# RS232_v10.net
KiCad netlist of a schematic drawn in EAGLE
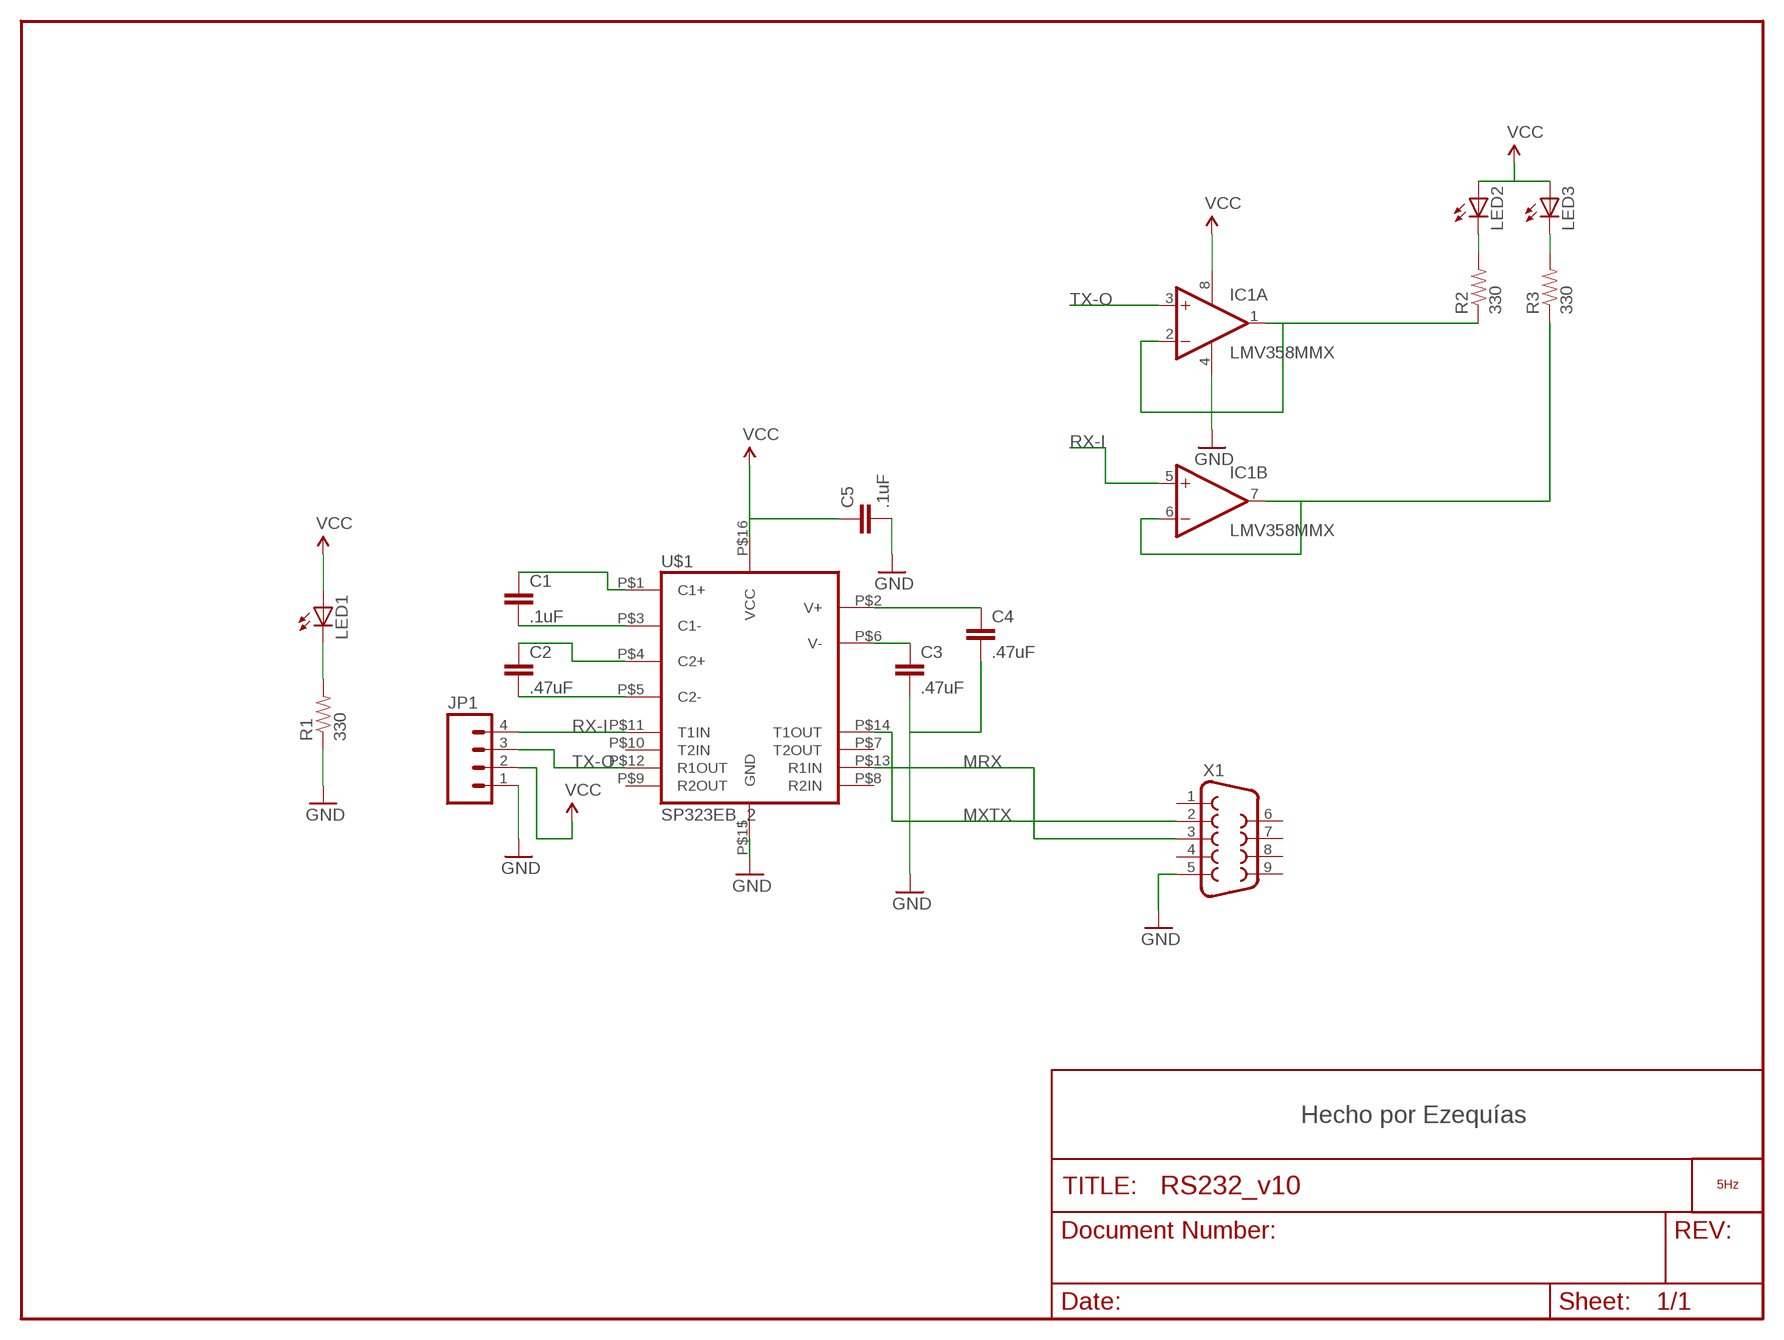
[diagram p0: schematic, sheet 1]

(export (version "E")
  (design (tool "Eeschema 10.0.6"))
  (components
    (comp (ref "C1")
      (value ".1uF")
      (footprint "eagle-import:0603-CAP")
      (libsource (lib "eagle-import") (part "CAP0603-CAP"))
    )
    (comp (ref "C2")
      (value ".47uF")
      (footprint "eagle-import:0603-CAP")
      (libsource (lib "eagle-import") (part "CAP0603-CAP"))
    )
    (comp (ref "C3")
      (value ".47uF")
      (footprint "eagle-import:0603-CAP")
      (libsource (lib "eagle-import") (part "CAP0603-CAP"))
    )
    (comp (ref "C4")
      (value ".47uF")
      (footprint "eagle-import:0603-CAP")
      (libsource (lib "eagle-import") (part "CAP0603-CAP"))
    )
    (comp (ref "C5")
      (value ".1uF")
      (footprint "eagle-import:0603-CAP")
      (libsource (lib "eagle-import") (part "CAP0603-CAP"))
    )
    (comp (ref "IC1")
      (value "LMV358MMX")
      (footprint "eagle-import:MSOP08")
      (libsource (lib "eagle-import") (part "LMV358?MMX"))
    )
    (comp (ref "JP1")
      (value "M04PTH")
      (footprint "eagle-import:1X04")
      (libsource (lib "eagle-import") (part "M04PTH"))
    )
    (comp (ref "LED1")
      (value "LED0603")
      (footprint "eagle-import:LED-0603")
      (libsource (lib "eagle-import") (part "LED0603"))
    )
    (comp (ref "LED2")
      (value "LED0603")
      (footprint "eagle-import:LED-0603")
      (libsource (lib "eagle-import") (part "LED0603"))
    )
    (comp (ref "LED3")
      (value "LED0603")
      (footprint "eagle-import:LED-0603")
      (libsource (lib "eagle-import") (part "LED0603"))
    )
    (comp (ref "LOGO1")
      (value "LOGO_5HZ_MAIN_15MM")
      (footprint "eagle-import:5HZ_LOGO_MAIN_15MM")
      (libsource (lib "eagle-import") (part "LOGO_5HZ_MAIN_15MM"))
    )
    (comp (ref "R1")
      (value "330")
      (footprint "eagle-import:0603-RES")
      (libsource (lib "eagle-import") (part "RESISTOR0603-RES"))
    )
    (comp (ref "R2")
      (value "330")
      (footprint "eagle-import:0603-RES")
      (libsource (lib "eagle-import") (part "RESISTOR0603-RES"))
    )
    (comp (ref "R3")
      (value "330")
      (footprint "eagle-import:0603-RES")
      (libsource (lib "eagle-import") (part "RESISTOR0603-RES"))
    )
    (comp (ref "U$1")
      (value "SP323EB_2")
      (footprint "eagle-import:SSOP-16")
      (libsource (lib "eagle-import") (part "SP323EB_2"))
    )
    (comp (ref "X1")
      (value "DB9FEMALE")
      (footprint "eagle-import:DB9")
      (libsource (lib "eagle-import") (part "DB9FEMALE"))
    )
  )
  (nets
    (net (code "1") (name "/MRX") (class "Default")
      (node (ref "U$1") (pin "P$13") (pinfunction "R1IN_P$13") (pintype "input"))
      (node (ref "X1") (pin "3") (pinfunction "3_3") (pintype "passive"))
    )
    (net (code "2") (name "/MXTX") (class "Default")
      (node (ref "U$1") (pin "P$14") (pinfunction "T1OUT_P$14") (pintype "output"))
      (node (ref "X1") (pin "2") (pinfunction "2_2") (pintype "passive"))
    )
    (net (code "3") (name "/RX-I") (class "Default")
      (node (ref "IC1") (pin "5") (pinfunction "+IN_5") (pintype "input"))
      (node (ref "JP1") (pin "4") (pinfunction "4_4") (pintype "passive"))
      (node (ref "U$1") (pin "P$11") (pinfunction "T1IN_P$11") (pintype "input"))
    )
    (net (code "4") (name "/TX-O") (class "Default")
      (node (ref "IC1") (pin "3") (pinfunction "+IN_3") (pintype "input"))
      (node (ref "JP1") (pin "3") (pinfunction "3_3") (pintype "passive"))
      (node (ref "U$1") (pin "P$12") (pinfunction "R1OUT_P$12") (pintype "output"))
    )
    (net (code "5") (name "GND") (class "Default")
      (node (ref "C3") (pin "2") (pinfunction "2_2") (pintype "passive"))
      (node (ref "C4") (pin "2") (pinfunction "2_2") (pintype "passive"))
      (node (ref "C5") (pin "2") (pinfunction "2_2") (pintype "passive"))
      (node (ref "IC1") (pin "4") (pinfunction "V-_4") (pintype "power_in"))
      (node (ref "JP1") (pin "1") (pinfunction "1_1") (pintype "passive"))
      (node (ref "R1") (pin "1") (pinfunction "1_1") (pintype "passive"))
      (node (ref "U$1") (pin "P$15") (pinfunction "GND_P$15") (pintype "bidirectional"))
      (node (ref "X1") (pin "5") (pinfunction "5_5") (pintype "passive"))
    )
    (net (code "6") (name "Net-(IC1A--IN)") (class "Default")
      (node (ref "IC1") (pin "1") (pinfunction "OUT_1") (pintype "output"))
      (node (ref "IC1") (pin "2") (pinfunction "-IN_2") (pintype "input"))
      (node (ref "R2") (pin "1") (pinfunction "1_1") (pintype "passive"))
    )
    (net (code "7") (name "Net-(IC1B--IN)") (class "Default")
      (node (ref "IC1") (pin "6") (pinfunction "-IN_6") (pintype "input"))
      (node (ref "IC1") (pin "7") (pinfunction "OUT_7") (pintype "output"))
      (node (ref "R3") (pin "1") (pinfunction "1_1") (pintype "passive"))
    )
    (net (code "8") (name "Net-(LED1-PadC)") (class "Default")
      (node (ref "LED1") (pin "C") (pinfunction "C_C") (pintype "passive"))
      (node (ref "R1") (pin "2") (pinfunction "2_2") (pintype "passive"))
    )
    (net (code "9") (name "Net-(LED2-PadC)") (class "Default")
      (node (ref "LED2") (pin "C") (pinfunction "C_C") (pintype "passive"))
      (node (ref "R2") (pin "2") (pinfunction "2_2") (pintype "passive"))
    )
    (net (code "10") (name "Net-(LED3-PadC)") (class "Default")
      (node (ref "LED3") (pin "C") (pinfunction "C_C") (pintype "passive"))
      (node (ref "R3") (pin "2") (pinfunction "2_2") (pintype "passive"))
    )
    (net (code "11") (name "Net-(U$1-C1+)") (class "Default")
      (node (ref "C1") (pin "1") (pinfunction "1_1") (pintype "passive"))
      (node (ref "U$1") (pin "P$1") (pinfunction "C1+_P$1") (pintype "bidirectional"))
    )
    (net (code "12") (name "Net-(U$1-C1-)") (class "Default")
      (node (ref "C1") (pin "2") (pinfunction "2_2") (pintype "passive"))
      (node (ref "U$1") (pin "P$3") (pinfunction "C1-_P$3") (pintype "bidirectional"))
    )
    (net (code "13") (name "Net-(U$1-C2+)") (class "Default")
      (node (ref "C2") (pin "1") (pinfunction "1_1") (pintype "passive"))
      (node (ref "U$1") (pin "P$4") (pinfunction "C2+_P$4") (pintype "bidirectional"))
    )
    (net (code "14") (name "Net-(U$1-C2-)") (class "Default")
      (node (ref "C2") (pin "2") (pinfunction "2_2") (pintype "passive"))
      (node (ref "U$1") (pin "P$5") (pinfunction "C2-_P$5") (pintype "bidirectional"))
    )
    (net (code "15") (name "Net-(U$1-V+)") (class "Default")
      (node (ref "C4") (pin "1") (pinfunction "1_1") (pintype "passive"))
      (node (ref "U$1") (pin "P$2") (pinfunction "V+_P$2") (pintype "bidirectional"))
    )
    (net (code "16") (name "Net-(U$1-V-)") (class "Default")
      (node (ref "C3") (pin "1") (pinfunction "1_1") (pintype "passive"))
      (node (ref "U$1") (pin "P$6") (pinfunction "V-_P$6") (pintype "bidirectional"))
    )
    (net (code "17") (name "VCC") (class "Default")
      (node (ref "C5") (pin "1") (pinfunction "1_1") (pintype "passive"))
      (node (ref "IC1") (pin "8") (pinfunction "V+_8") (pintype "power_in"))
      (node (ref "JP1") (pin "2") (pinfunction "2_2") (pintype "passive"))
      (node (ref "LED1") (pin "A") (pinfunction "A_A") (pintype "passive"))
      (node (ref "LED2") (pin "A") (pinfunction "A_A") (pintype "passive"))
      (node (ref "LED3") (pin "A") (pinfunction "A_A") (pintype "passive"))
      (node (ref "U$1") (pin "P$16") (pinfunction "VCC_P$16") (pintype "bidirectional"))
    )
    (net (code "18") (name "unconnected-(U$1-R2IN-PadP$8)") (class "Default")
      (node (ref "U$1") (pin "P$8") (pinfunction "R2IN_P$8") (pintype "input"))
    )
    (net (code "19") (name "unconnected-(U$1-R2OUT-PadP$9)") (class "Default")
      (node (ref "U$1") (pin "P$9") (pinfunction "R2OUT_P$9") (pintype "output"))
    )
    (net (code "20") (name "unconnected-(U$1-T2IN-PadP$10)") (class "Default")
      (node (ref "U$1") (pin "P$10") (pinfunction "T2IN_P$10") (pintype "input"))
    )
    (net (code "21") (name "unconnected-(U$1-T2OUT-PadP$7)") (class "Default")
      (node (ref "U$1") (pin "P$7") (pinfunction "T2OUT_P$7") (pintype "output"))
    )
    (net (code "22") (name "unconnected-(X1-Pad1)") (class "Default")
      (node (ref "X1") (pin "1") (pinfunction "1_1") (pintype "passive"))
    )
    (net (code "23") (name "unconnected-(X1-Pad4)") (class "Default")
      (node (ref "X1") (pin "4") (pinfunction "4_4") (pintype "passive"))
    )
    (net (code "24") (name "unconnected-(X1-Pad6)") (class "Default")
      (node (ref "X1") (pin "6") (pinfunction "6_6") (pintype "passive"))
    )
    (net (code "25") (name "unconnected-(X1-Pad7)") (class "Default")
      (node (ref "X1") (pin "7") (pinfunction "7_7") (pintype "passive"))
    )
    (net (code "26") (name "unconnected-(X1-Pad8)") (class "Default")
      (node (ref "X1") (pin "8") (pinfunction "8_8") (pintype "passive"))
    )
    (net (code "27") (name "unconnected-(X1-Pad9)") (class "Default")
      (node (ref "X1") (pin "9") (pinfunction "9_9") (pintype "passive"))
    )
  )
)
